# supercap.net
KiCad netlist of a schematic drawn in Altium Designer
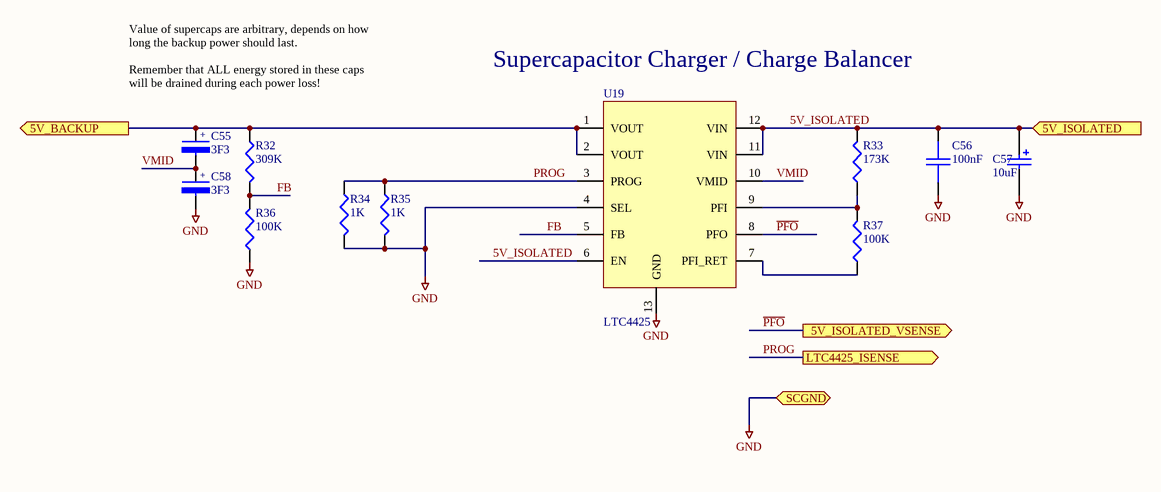
[diagram p0: supercap.SchDoc]

(export (version "E")
  (design (tool "Eeschema 10.0.6"))
  (components
    (comp (ref "C55")
      (value "3F3")
      (footprint "ELECTROLYTIC-5-32")
      (description "Supercap")
      (libsource (lib "RCLDQ") (part "CAP-POL"))
    )
    (comp (ref "C56")
      (value "100nF")
      (footprint "0603")
      (description "Capacitor")
      (libsource (lib "RCLDQ") (part "CAP"))
    )
    (comp (ref "C57")
      (value "10uF")
      (footprint "MCCT-CASEA")
      (description "Polarized Capacitor (Surface Mount)")
      (libsource (lib "RCLDQ") (part "CAP POL3"))
    )
    (comp (ref "C58")
      (value "3F3")
      (footprint "ELECTROLYTIC-5-32")
      (description "Supercap")
      (libsource (lib "RCLDQ") (part "CAP-POL"))
    )
    (comp (ref "R32")
      (value "309K")
      (footprint "0603")
      (description "Resistor")
      (libsource (lib "RCLDQ") (part "RES1"))
    )
    (comp (ref "R33")
      (value "173K")
      (footprint "0805")
      (description "Resistor")
      (libsource (lib "RCLDQ") (part "RES1"))
    )
    (comp (ref "R34")
      (value "1K")
      (footprint "0603")
      (description "Resistor")
      (libsource (lib "RCLDQ") (part "RES1"))
    )
    (comp (ref "R35")
      (value "1K")
      (footprint "0603")
      (description "Resistor")
      (libsource (lib "RCLDQ") (part "RES1"))
    )
    (comp (ref "R36")
      (value "100K")
      (footprint "0603")
      (description "Resistor")
      (libsource (lib "RCLDQ") (part "RES1"))
    )
    (comp (ref "R37")
      (value "100K")
      (footprint "0603")
      (description "Resistor")
      (libsource (lib "RCLDQ") (part "RES1"))
    )
    (comp (ref "U19")
      (value "LTC4425")
      (footprint "MS-12")
      (description "Supercapacitor Charger")
      (libsource (lib "sion") (part "LTC4425"))
    )
  )
  (nets
    (net (code "1") (name "/5V_BACKUP") (class "Default")
      (node (ref "C55") (pin "1") (pinfunction "1_1") (pintype "passive"))
      (node (ref "R32") (pin "1") (pinfunction "1_1") (pintype "passive"))
      (node (ref "U19") (pin "1") (pinfunction "VOUT_1") (pintype "passive"))
      (node (ref "U19") (pin "2") (pinfunction "VOUT_2") (pintype "passive"))
    )
    (net (code "2") (name "/5V_ISOLATED") (class "Default")
      (node (ref "C56") (pin "1") (pinfunction "1_1") (pintype "passive"))
      (node (ref "C57") (pin "1") (pinfunction "1_1") (pintype "passive"))
      (node (ref "R33") (pin "2") (pinfunction "2_2") (pintype "passive"))
      (node (ref "U19") (pin "11") (pinfunction "VIN_11") (pintype "passive"))
      (node (ref "U19") (pin "12") (pinfunction "VIN_12") (pintype "passive"))
      (node (ref "U19") (pin "6") (pinfunction "EN_6") (pintype "passive"))
    )
    (net (code "3") (name "/FB") (class "Default")
      (node (ref "R32") (pin "2") (pinfunction "2_2") (pintype "passive"))
      (node (ref "R36") (pin "2") (pinfunction "2_2") (pintype "passive"))
      (node (ref "U19") (pin "5") (pinfunction "FB_5") (pintype "passive"))
    )
    (net (code "4") (name "/PROG") (class "Default")
      (node (ref "R34") (pin "1") (pinfunction "1_1") (pintype "passive"))
      (node (ref "R35") (pin "1") (pinfunction "1_1") (pintype "passive"))
      (node (ref "U19") (pin "3") (pinfunction "PROG_3") (pintype "passive"))
    )
    (net (code "5") (name "/VMID") (class "Default")
      (node (ref "C55") (pin "2") (pinfunction "2_2") (pintype "passive"))
      (node (ref "C58") (pin "1") (pinfunction "1_1") (pintype "passive"))
      (node (ref "U19") (pin "10") (pinfunction "VMID_10") (pintype "passive"))
    )
    (net (code "6") (name "/~{PFO}") (class "Default")
      (node (ref "U19") (pin "8") (pinfunction "PFO_8") (pintype "passive"))
    )
    (net (code "7") (name "GND") (class "Default")
      (node (ref "C56") (pin "2") (pinfunction "2_2") (pintype "passive"))
      (node (ref "C57") (pin "2") (pinfunction "2_2") (pintype "passive"))
      (node (ref "C58") (pin "2") (pinfunction "2_2") (pintype "passive"))
      (node (ref "R34") (pin "2") (pinfunction "2_2") (pintype "passive"))
      (node (ref "R35") (pin "2") (pinfunction "2_2") (pintype "passive"))
      (node (ref "R36") (pin "1") (pinfunction "1_1") (pintype "passive"))
      (node (ref "U19") (pin "13") (pinfunction "GND_13") (pintype "passive"))
      (node (ref "U19") (pin "4") (pinfunction "SEL_4") (pintype "passive"))
    )
    (net (code "8") (name "Net-(U19-PFI)") (class "Default")
      (node (ref "R33") (pin "1") (pinfunction "1_1") (pintype "passive"))
      (node (ref "R37") (pin "2") (pinfunction "2_2") (pintype "passive"))
      (node (ref "U19") (pin "9") (pinfunction "PFI_9") (pintype "passive"))
    )
    (net (code "9") (name "Net-(U19-PFI_RET)") (class "Default")
      (node (ref "R37") (pin "1") (pinfunction "1_1") (pintype "passive"))
      (node (ref "U19") (pin "7") (pinfunction "PFI_RET_7") (pintype "passive"))
    )
  )
)
